# sensoresard.net
KiCad netlist of a schematic drawn in EAGLE
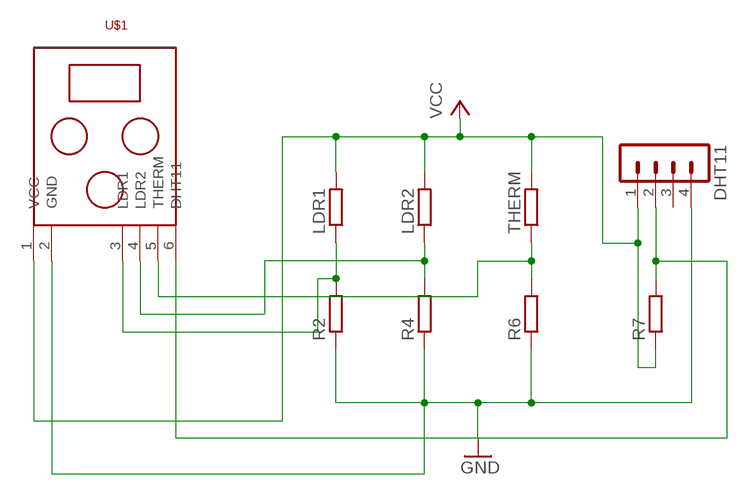
[diagram p0: schematic, sheet 1]

(export (version "E")
  (design (tool "Eeschema 10.0.6"))
  (components
    (comp (ref "DHT11")
      (value "MA04-1")
      (footprint "eagle-import:MA04-1")
      (libsource (lib "eagle-import") (part "MA04-1"))
    )
    (comp (ref "LDR1")
      (value "R-EU_0204/7")
      (footprint "eagle-import:0204_7")
      (libsource (lib "eagle-import") (part "R-EU_0204/7"))
    )
    (comp (ref "LDR2")
      (value "R-EU_0204/7")
      (footprint "eagle-import:0204_7")
      (libsource (lib "eagle-import") (part "R-EU_0204/7"))
    )
    (comp (ref "R2")
      (value "R-EU_0204/7")
      (footprint "eagle-import:0204_7")
      (libsource (lib "eagle-import") (part "R-EU_0204/7"))
    )
    (comp (ref "R4")
      (value "R-EU_0204/7")
      (footprint "eagle-import:0204_7")
      (libsource (lib "eagle-import") (part "R-EU_0204/7"))
    )
    (comp (ref "R6")
      (value "R-EU_0204/7")
      (footprint "eagle-import:0204_7")
      (libsource (lib "eagle-import") (part "R-EU_0204/7"))
    )
    (comp (ref "R7")
      (value "R-EU_0204/7")
      (footprint "eagle-import:0204_7")
      (libsource (lib "eagle-import") (part "R-EU_0204/7"))
    )
    (comp (ref "THERM")
      (value "R-EU_0204/7")
      (footprint "eagle-import:0204_7")
      (libsource (lib "eagle-import") (part "R-EU_0204/7"))
    )
    (comp (ref "U$1") (value "PA") (footprint "eagle-import:PA") (libsource (lib "eagle-import") (part "PA")))
  )
  (nets
    (net (code "1") (name "GND") (class "Default")
      (node (ref "DHT11") (pin "4") (pinfunction "4_4") (pintype "passive"))
      (node (ref "R2") (pin "1") (pinfunction "1_1") (pintype "passive"))
      (node (ref "R4") (pin "1") (pinfunction "1_1") (pintype "passive"))
      (node (ref "R6") (pin "1") (pinfunction "1_1") (pintype "passive"))
      (node (ref "U$1") (pin "2") (pinfunction "GND_2") (pintype "bidirectional"))
    )
    (net (code "2") (name "Net-(U$1-DHT11)") (class "Default")
      (node (ref "DHT11") (pin "2") (pinfunction "2_2") (pintype "passive"))
      (node (ref "R7") (pin "2") (pinfunction "2_2") (pintype "passive"))
      (node (ref "U$1") (pin "6") (pinfunction "DHT11_6") (pintype "bidirectional"))
    )
    (net (code "3") (name "Net-(U$1-LDR1)") (class "Default")
      (node (ref "LDR1") (pin "1") (pinfunction "1_1") (pintype "passive"))
      (node (ref "R2") (pin "2") (pinfunction "2_2") (pintype "passive"))
      (node (ref "U$1") (pin "3") (pinfunction "LDR1_3") (pintype "bidirectional"))
    )
    (net (code "4") (name "Net-(U$1-LDR2)") (class "Default")
      (node (ref "LDR2") (pin "1") (pinfunction "1_1") (pintype "passive"))
      (node (ref "R4") (pin "2") (pinfunction "2_2") (pintype "passive"))
      (node (ref "U$1") (pin "4") (pinfunction "LDR2_4") (pintype "bidirectional"))
    )
    (net (code "5") (name "Net-(U$1-THERM)") (class "Default")
      (node (ref "R6") (pin "2") (pinfunction "2_2") (pintype "passive"))
      (node (ref "THERM") (pin "1") (pinfunction "1_1") (pintype "passive"))
      (node (ref "U$1") (pin "5") (pinfunction "THERM_5") (pintype "bidirectional"))
    )
    (net (code "6") (name "VCC") (class "Default")
      (node (ref "DHT11") (pin "1") (pinfunction "1_1") (pintype "passive"))
      (node (ref "LDR1") (pin "2") (pinfunction "2_2") (pintype "passive"))
      (node (ref "LDR2") (pin "2") (pinfunction "2_2") (pintype "passive"))
      (node (ref "R7") (pin "1") (pinfunction "1_1") (pintype "passive"))
      (node (ref "THERM") (pin "2") (pinfunction "2_2") (pintype "passive"))
      (node (ref "U$1") (pin "1") (pinfunction "VCC_1") (pintype "bidirectional"))
    )
    (net (code "7") (name "unconnected-(DHT11-Pad3)") (class "Default")
      (node (ref "DHT11") (pin "3") (pinfunction "3_3") (pintype "passive"))
    )
  )
)
